# 24_064_HEAT.net
KiCad netlist of a schematic drawn in Altium Designer
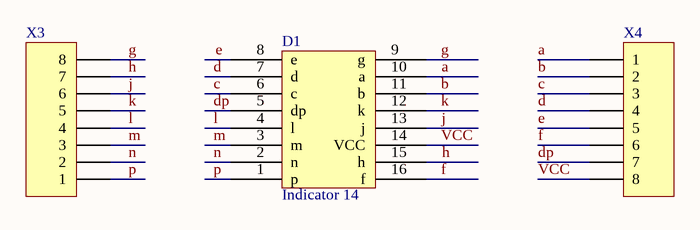
[diagram p0: 24.064_HEAT.SchDoc]

(export (version "E")
  (design (tool "Eeschema 10.0.6"))
  (components
    (comp (ref "D1")
      (value "Indicator 14")
      (footprint "INDICATIR 14")
      (libsource (lib "msp_SchLib") (part "Indicator 14"))
    )
    (comp (ref "X3")
      (value "Header 8")
      (footprint "HDR1X8")
      (description "Header, 8-Pin")
      (fields (field (name "PUBLISHER") "Altium Limited"))
      (libsource (lib "Miscellaneous Connectors") (part "Header 8"))
    )
    (comp (ref "X4")
      (value "Header 8")
      (footprint "HDR1X8")
      (description "Header, 8-Pin")
      (fields (field (name "PUBLISHER") "Altium Limited"))
      (libsource (lib "") (part "Header 8_1"))
    )
  )
  (nets
    (net (code "1") (name "/VCC") (class "Default")
      (node (ref "D1") (pin "14") (pinfunction "VCC_14") (pintype "passive"))
      (node (ref "X4") (pin "8") (pinfunction "8_8") (pintype "passive"))
    )
    (net (code "2") (name "/a") (class "Default")
      (node (ref "D1") (pin "10") (pinfunction "a_10") (pintype "passive"))
      (node (ref "X4") (pin "1") (pinfunction "1_1") (pintype "passive"))
    )
    (net (code "3") (name "/b") (class "Default")
      (node (ref "D1") (pin "11") (pinfunction "b_11") (pintype "passive"))
      (node (ref "X4") (pin "2") (pinfunction "2_2") (pintype "passive"))
    )
    (net (code "4") (name "/c") (class "Default")
      (node (ref "D1") (pin "6") (pinfunction "c_6") (pintype "passive"))
      (node (ref "X4") (pin "3") (pinfunction "3_3") (pintype "passive"))
    )
    (net (code "5") (name "/d") (class "Default")
      (node (ref "D1") (pin "7") (pinfunction "d_7") (pintype "passive"))
      (node (ref "X4") (pin "4") (pinfunction "4_4") (pintype "passive"))
    )
    (net (code "6") (name "/dp") (class "Default")
      (node (ref "D1") (pin "5") (pinfunction "dp_5") (pintype "passive"))
      (node (ref "X4") (pin "7") (pinfunction "7_7") (pintype "passive"))
    )
    (net (code "7") (name "/e") (class "Default")
      (node (ref "D1") (pin "8") (pinfunction "e_8") (pintype "passive"))
      (node (ref "X4") (pin "5") (pinfunction "5_5") (pintype "passive"))
    )
    (net (code "8") (name "/f") (class "Default")
      (node (ref "D1") (pin "16") (pinfunction "f_16") (pintype "passive"))
      (node (ref "X4") (pin "6") (pinfunction "6_6") (pintype "passive"))
    )
    (net (code "9") (name "/g") (class "Default")
      (node (ref "D1") (pin "9") (pinfunction "g_9") (pintype "passive"))
      (node (ref "X3") (pin "8") (pinfunction "8_8") (pintype "passive"))
    )
    (net (code "10") (name "/h") (class "Default")
      (node (ref "D1") (pin "15") (pinfunction "h_15") (pintype "passive"))
      (node (ref "X3") (pin "7") (pinfunction "7_7") (pintype "passive"))
    )
    (net (code "11") (name "/j") (class "Default")
      (node (ref "D1") (pin "13") (pinfunction "j_13") (pintype "passive"))
      (node (ref "X3") (pin "6") (pinfunction "6_6") (pintype "passive"))
    )
    (net (code "12") (name "/k") (class "Default")
      (node (ref "D1") (pin "12") (pinfunction "k_12") (pintype "passive"))
      (node (ref "X3") (pin "5") (pinfunction "5_5") (pintype "passive"))
    )
    (net (code "13") (name "/l") (class "Default")
      (node (ref "D1") (pin "4") (pinfunction "l_4") (pintype "passive"))
      (node (ref "X3") (pin "4") (pinfunction "4_4") (pintype "passive"))
    )
    (net (code "14") (name "/m") (class "Default")
      (node (ref "D1") (pin "3") (pinfunction "m_3") (pintype "passive"))
      (node (ref "X3") (pin "3") (pinfunction "3_3") (pintype "passive"))
    )
    (net (code "15") (name "/n") (class "Default")
      (node (ref "D1") (pin "2") (pinfunction "n_2") (pintype "passive"))
      (node (ref "X3") (pin "2") (pinfunction "2_2") (pintype "passive"))
    )
    (net (code "16") (name "/p") (class "Default")
      (node (ref "D1") (pin "1") (pinfunction "p_1") (pintype "passive"))
      (node (ref "X3") (pin "1") (pinfunction "1_1") (pintype "passive"))
    )
  )
)
